# kicker.net
KiCad netlist of a schematic drawn in EAGLE
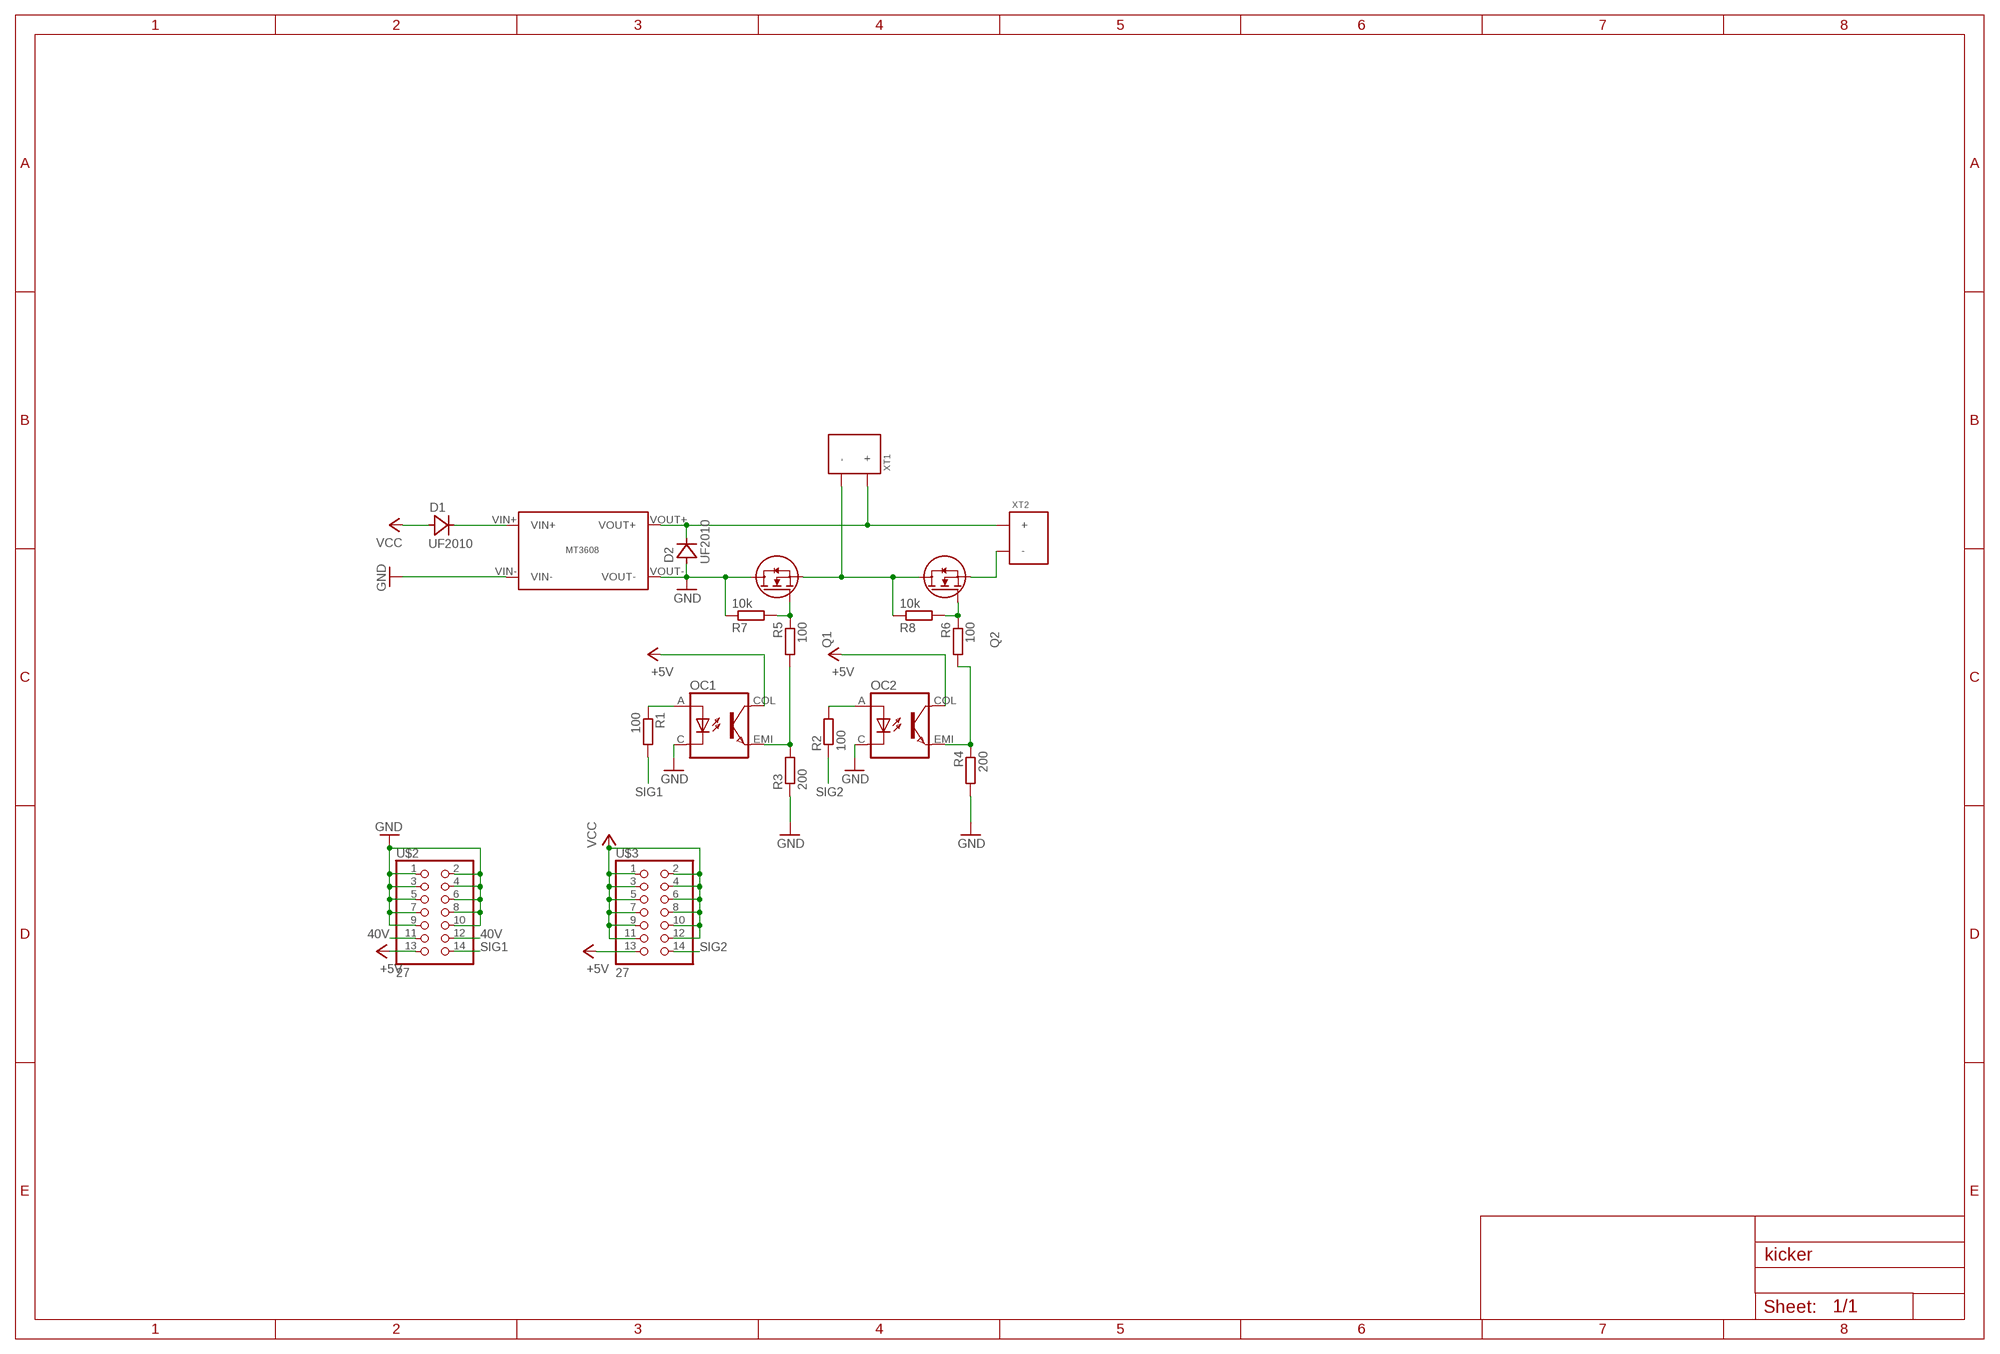
[diagram p0: schematic, sheet 1]

(export (version "E")
  (design (tool "Eeschema 10.0.6"))
  (components
    (comp (ref "D1")
      (value "UF2010")
      (footprint "eagle-import:UF2010")
      (libsource (lib "eagle-import") (part "UF2010"))
    )
    (comp (ref "D2")
      (value "UF2010")
      (footprint "eagle-import:UF2010")
      (libsource (lib "eagle-import") (part "UF2010"))
    )
    (comp (ref "OC1")
      (value "TL293(GB)")
      (footprint "eagle-import:SOIC127P700X230-4N")
      (libsource (lib "eagle-import") (part "TL293(GB)"))
    )
    (comp (ref "OC2")
      (value "TL293(GB)")
      (footprint "eagle-import:SOIC127P700X230-4N")
      (libsource (lib "eagle-import") (part "TL293(GB)"))
    )
    (comp (ref "Q1")
      (value "NP52N06SLG")
      (footprint "eagle-import:TO230P1040X230-3N")
      (libsource (lib "eagle-import") (part "NP52N06SLG"))
    )
    (comp (ref "Q2")
      (value "NP52N06SLG")
      (footprint "eagle-import:TO230P1040X230-3N")
      (libsource (lib "eagle-import") (part "NP52N06SLG"))
    )
    (comp (ref "R1")
      (value "100")
      (footprint "eagle-import:R0603")
      (libsource (lib "eagle-import") (part "R-EU_R0603"))
    )
    (comp (ref "R2")
      (value "100")
      (footprint "eagle-import:R0603")
      (libsource (lib "eagle-import") (part "R-EU_R0603"))
    )
    (comp (ref "R3")
      (value "200")
      (footprint "eagle-import:R0603")
      (libsource (lib "eagle-import") (part "R-EU_R0603"))
    )
    (comp (ref "R4")
      (value "200")
      (footprint "eagle-import:R0603")
      (libsource (lib "eagle-import") (part "R-EU_R0603"))
    )
    (comp (ref "R5")
      (value "100")
      (footprint "eagle-import:R0603")
      (libsource (lib "eagle-import") (part "R-EU_R0603"))
    )
    (comp (ref "R6")
      (value "100")
      (footprint "eagle-import:R0603")
      (libsource (lib "eagle-import") (part "R-EU_R0603"))
    )
    (comp (ref "R7")
      (value "10k")
      (footprint "eagle-import:R0603")
      (libsource (lib "eagle-import") (part "R-EU_R0603"))
    )
    (comp (ref "R8")
      (value "10k")
      (footprint "eagle-import:R0603")
      (libsource (lib "eagle-import") (part "R-EU_R0603"))
    )
    (comp (ref "U$1")
      (value "MT3608")
      (footprint "eagle-import:MT3608")
      (libsource (lib "eagle-import") (part "MT3608"))
    )
    (comp (ref "U$2")
      (value "27")
      (footprint "eagle-import:2_7")
      (libsource (lib "eagle-import") (part "27"))
    )
    (comp (ref "U$3")
      (value "27")
      (footprint "eagle-import:2_7")
      (libsource (lib "eagle-import") (part "27"))
    )
    (comp (ref "XT1")
      (value "XT30PW-F")
      (footprint "eagle-import:XT30PW-F")
      (libsource (lib "eagle-import") (part "XT30PW-F"))
    )
    (comp (ref "XT2")
      (value "XT30PW-F")
      (footprint "eagle-import:XT30PW-F")
      (libsource (lib "eagle-import") (part "XT30PW-F"))
    )
  )
  (nets
    (net (code "1") (name "+5V") (class "Default")
      (node (ref "OC1") (pin "COL") (pinfunction "COL_COL") (pintype "passive"))
      (node (ref "OC2") (pin "COL") (pinfunction "COL_COL") (pintype "passive"))
      (node (ref "U$2") (pin "13") (pinfunction "13_13") (pintype "passive"))
      (node (ref "U$3") (pin "13") (pinfunction "13_13") (pintype "passive"))
    )
    (net (code "2") (name "/40V") (class "Default")
      (node (ref "D2") (pin "C") (pinfunction "C_C") (pintype "passive"))
      (node (ref "U$1") (pin "VOUT+") (pinfunction "VOUT+_VOUT+") (pintype "bidirectional"))
      (node (ref "U$2") (pin "11") (pinfunction "11_11") (pintype "passive"))
      (node (ref "U$2") (pin "12") (pinfunction "12_12") (pintype "passive"))
      (node (ref "XT1") (pin "+") (pinfunction "+_+") (pintype "bidirectional"))
      (node (ref "XT2") (pin "+") (pinfunction "+_+") (pintype "bidirectional"))
    )
    (net (code "3") (name "/SIG1") (class "Default")
      (node (ref "R1") (pin "2") (pinfunction "2_2") (pintype "passive"))
      (node (ref "U$2") (pin "14") (pinfunction "14_14") (pintype "passive"))
    )
    (net (code "4") (name "/SIG2") (class "Default")
      (node (ref "R2") (pin "1") (pinfunction "1_1") (pintype "passive"))
      (node (ref "U$3") (pin "14") (pinfunction "14_14") (pintype "passive"))
    )
    (net (code "5") (name "GND") (class "Default")
      (node (ref "D2") (pin "A") (pinfunction "A_A") (pintype "passive"))
      (node (ref "OC1") (pin "C") (pinfunction "C_C") (pintype "passive"))
      (node (ref "OC2") (pin "C") (pinfunction "C_C") (pintype "passive"))
      (node (ref "Q1") (pin "D") (pinfunction "D_D") (pintype "passive"))
      (node (ref "R3") (pin "1") (pinfunction "1_1") (pintype "passive"))
      (node (ref "R4") (pin "2") (pinfunction "2_2") (pintype "passive"))
      (node (ref "R7") (pin "1") (pinfunction "1_1") (pintype "passive"))
      (node (ref "U$1") (pin "VIN-") (pinfunction "VIN-_VIN-") (pintype "bidirectional"))
      (node (ref "U$1") (pin "VOUT-") (pinfunction "VOUT-_VOUT-") (pintype "bidirectional"))
      (node (ref "U$2") (pin "1") (pinfunction "1_1") (pintype "passive"))
      (node (ref "U$2") (pin "10") (pinfunction "10_10") (pintype "passive"))
      (node (ref "U$2") (pin "2") (pinfunction "2_2") (pintype "passive"))
      (node (ref "U$2") (pin "3") (pinfunction "3_3") (pintype "passive"))
      (node (ref "U$2") (pin "4") (pinfunction "4_4") (pintype "passive"))
      (node (ref "U$2") (pin "5") (pinfunction "5_5") (pintype "passive"))
      (node (ref "U$2") (pin "6") (pinfunction "6_6") (pintype "passive"))
      (node (ref "U$2") (pin "7") (pinfunction "7_7") (pintype "passive"))
      (node (ref "U$2") (pin "8") (pinfunction "8_8") (pintype "passive"))
      (node (ref "U$2") (pin "9") (pinfunction "9_9") (pintype "passive"))
    )
    (net (code "6") (name "Net-(D1-PadC)") (class "Default")
      (node (ref "D1") (pin "C") (pinfunction "C_C") (pintype "passive"))
      (node (ref "U$1") (pin "VIN+") (pinfunction "VIN+_VIN+") (pintype "bidirectional"))
    )
    (net (code "7") (name "Net-(OC1-PadA)") (class "Default")
      (node (ref "OC1") (pin "A") (pinfunction "A_A") (pintype "passive"))
      (node (ref "R1") (pin "1") (pinfunction "1_1") (pintype "passive"))
    )
    (net (code "8") (name "Net-(OC1-PadEMI)") (class "Default")
      (node (ref "OC1") (pin "EMI") (pinfunction "EMI_EMI") (pintype "passive"))
      (node (ref "R3") (pin "2") (pinfunction "2_2") (pintype "passive"))
      (node (ref "R5") (pin "2") (pinfunction "2_2") (pintype "passive"))
    )
    (net (code "9") (name "Net-(OC2-PadA)") (class "Default")
      (node (ref "OC2") (pin "A") (pinfunction "A_A") (pintype "passive"))
      (node (ref "R2") (pin "2") (pinfunction "2_2") (pintype "passive"))
    )
    (net (code "10") (name "Net-(OC2-PadEMI)") (class "Default")
      (node (ref "OC2") (pin "EMI") (pinfunction "EMI_EMI") (pintype "passive"))
      (node (ref "R4") (pin "1") (pinfunction "1_1") (pintype "passive"))
      (node (ref "R6") (pin "2") (pinfunction "2_2") (pintype "passive"))
    )
    (net (code "11") (name "Net-(Q1-PadG)") (class "Default")
      (node (ref "Q1") (pin "G") (pinfunction "G_G") (pintype "passive"))
      (node (ref "R5") (pin "1") (pinfunction "1_1") (pintype "passive"))
      (node (ref "R7") (pin "2") (pinfunction "2_2") (pintype "passive"))
    )
    (net (code "12") (name "Net-(Q1-PadS)") (class "Default")
      (node (ref "Q1") (pin "S") (pinfunction "S_S") (pintype "passive"))
      (node (ref "Q2") (pin "D") (pinfunction "D_D") (pintype "passive"))
      (node (ref "R8") (pin "1") (pinfunction "1_1") (pintype "passive"))
      (node (ref "XT1") (pin "-") (pinfunction "-_-") (pintype "bidirectional"))
    )
    (net (code "13") (name "Net-(Q2-PadG)") (class "Default")
      (node (ref "Q2") (pin "G") (pinfunction "G_G") (pintype "passive"))
      (node (ref "R6") (pin "1") (pinfunction "1_1") (pintype "passive"))
      (node (ref "R8") (pin "2") (pinfunction "2_2") (pintype "passive"))
    )
    (net (code "14") (name "Net-(Q2-PadS)") (class "Default")
      (node (ref "Q2") (pin "S") (pinfunction "S_S") (pintype "passive"))
      (node (ref "XT2") (pin "-") (pinfunction "-_-") (pintype "bidirectional"))
    )
    (net (code "15") (name "VCC") (class "Default")
      (node (ref "D1") (pin "A") (pinfunction "A_A") (pintype "passive"))
      (node (ref "U$3") (pin "1") (pinfunction "1_1") (pintype "passive"))
      (node (ref "U$3") (pin "10") (pinfunction "10_10") (pintype "passive"))
      (node (ref "U$3") (pin "11") (pinfunction "11_11") (pintype "passive"))
      (node (ref "U$3") (pin "12") (pinfunction "12_12") (pintype "passive"))
      (node (ref "U$3") (pin "2") (pinfunction "2_2") (pintype "passive"))
      (node (ref "U$3") (pin "3") (pinfunction "3_3") (pintype "passive"))
      (node (ref "U$3") (pin "4") (pinfunction "4_4") (pintype "passive"))
      (node (ref "U$3") (pin "5") (pinfunction "5_5") (pintype "passive"))
      (node (ref "U$3") (pin "6") (pinfunction "6_6") (pintype "passive"))
      (node (ref "U$3") (pin "7") (pinfunction "7_7") (pintype "passive"))
      (node (ref "U$3") (pin "8") (pinfunction "8_8") (pintype "passive"))
      (node (ref "U$3") (pin "9") (pinfunction "9_9") (pintype "passive"))
    )
  )
)
